# Probe.net
KiCad netlist of a schematic drawn in EAGLE
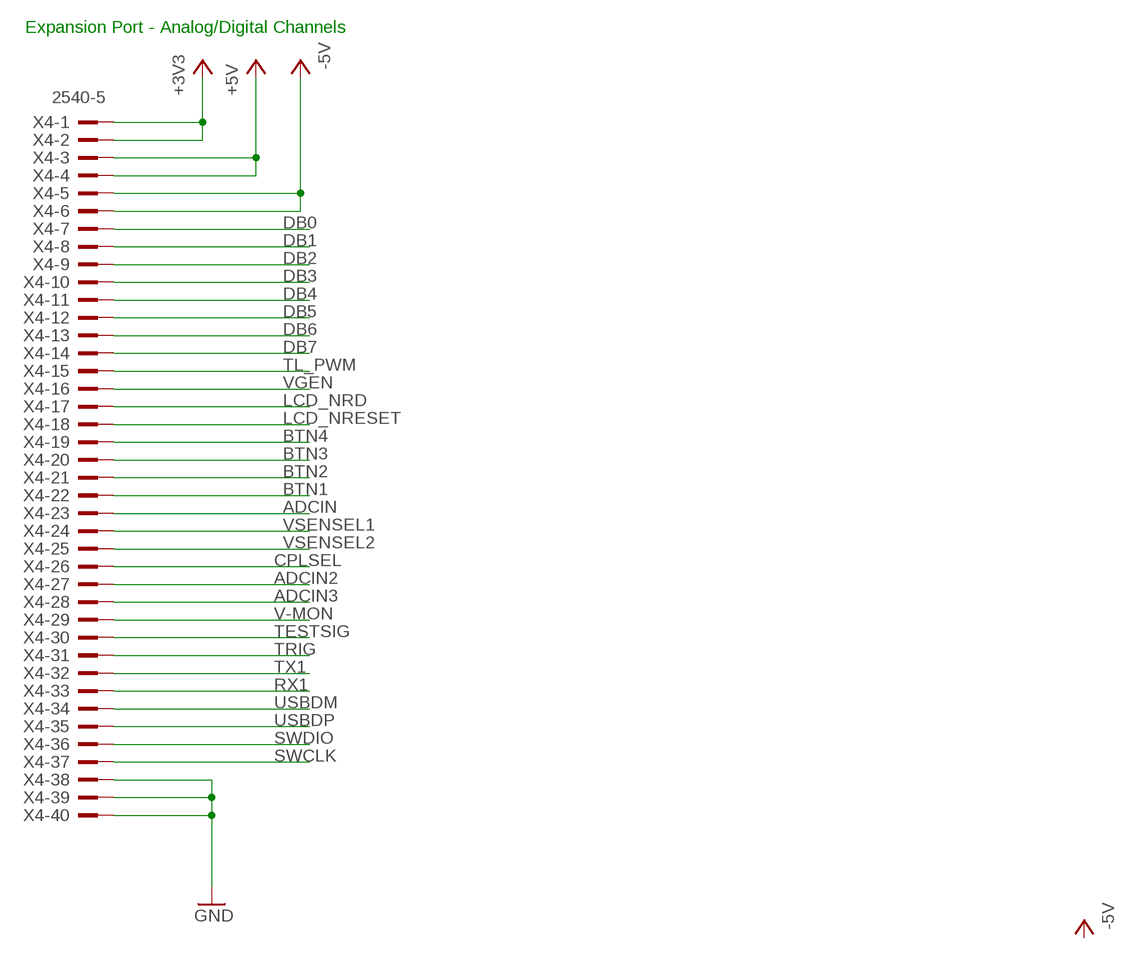
[diagram p0: schematic, sheet 1]
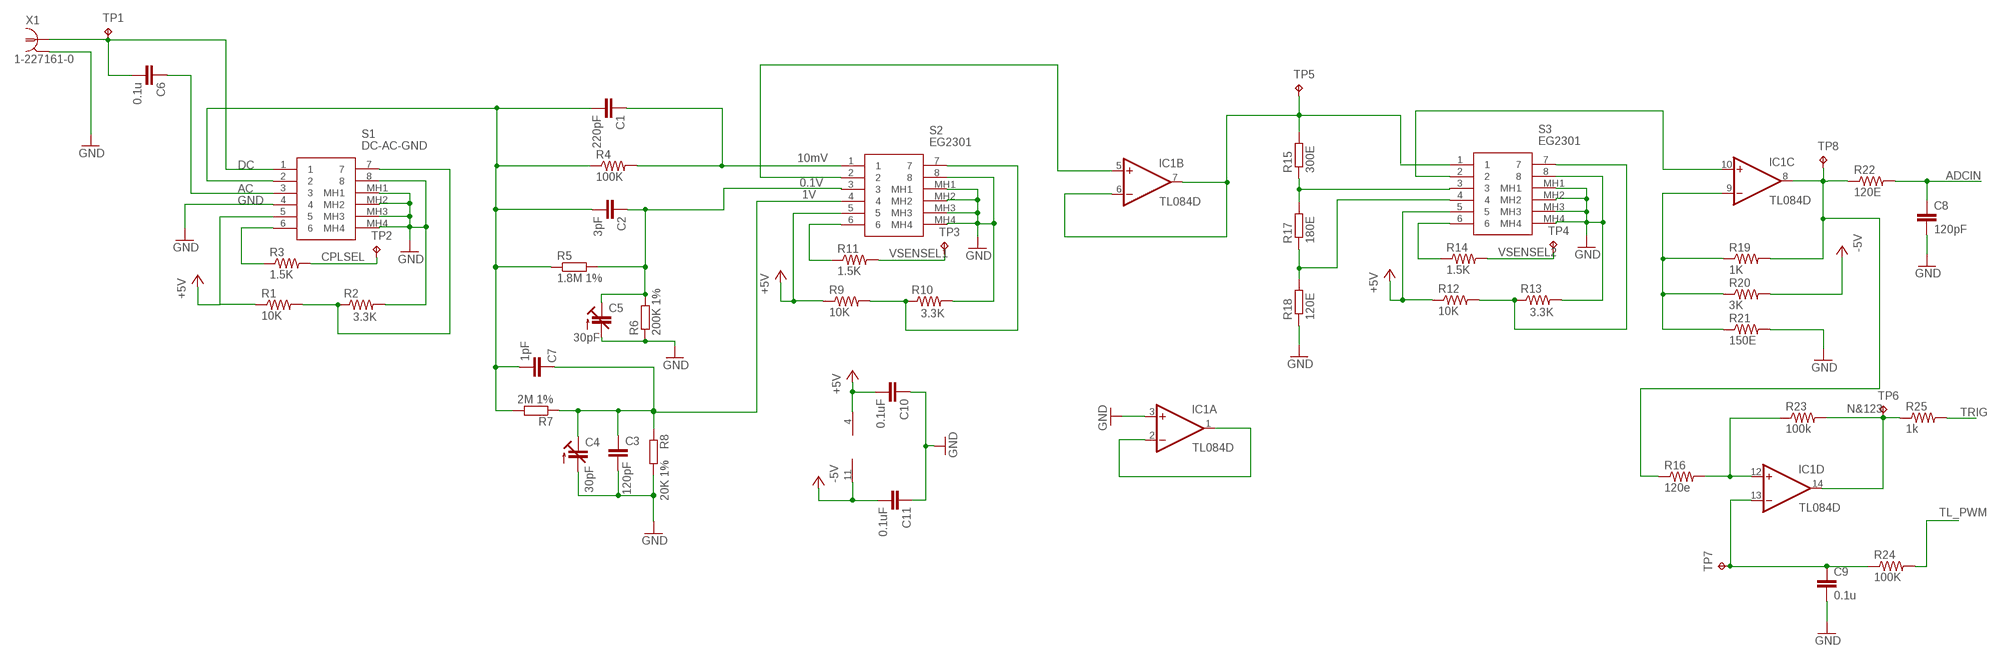
[diagram p1: schematic, sheet 2]

(export (version "E")
  (design (tool "Eeschema 10.0.6"))
  (components
    (comp (ref "C1")
      (value "220pF")
      (footprint "eagle-import:C1206")
      (libsource (lib "eagle-import") (part "C-EUC1206"))
    )
    (comp (ref "C2")
      (value "3pF")
      (footprint "eagle-import:C1206")
      (libsource (lib "eagle-import") (part "C-EUC1206"))
    )
    (comp (ref "C3")
      (value "120pF")
      (footprint "eagle-import:C2.5-3")
      (libsource (lib "eagle-import") (part "C2,5-3"))
    )
    (comp (ref "C4")
      (value "30pF")
      (footprint "eagle-import:CTRIM808-BC")
      (libsource (lib "eagle-import") (part "C-TRIMM808"))
    )
    (comp (ref "C5")
      (value "30pF")
      (footprint "eagle-import:CTRIM808-BC")
      (libsource (lib "eagle-import") (part "C-TRIMM808"))
    )
    (comp (ref "C6")
      (value "0.1u")
      (footprint "eagle-import:C1206")
      (libsource (lib "eagle-import") (part "C-EUC1206"))
    )
    (comp (ref "C7")
      (value "1pF")
      (footprint "eagle-import:C1206")
      (libsource (lib "eagle-import") (part "C-EUC1206"))
    )
    (comp (ref "C8")
      (value "120pF")
      (footprint "eagle-import:C2.5-3")
      (libsource (lib "eagle-import") (part "C2,5-3"))
    )
    (comp (ref "C9")
      (value "0.1u")
      (footprint "eagle-import:C2.5-3")
      (libsource (lib "eagle-import") (part "C2,5-3"))
    )
    (comp (ref "C10")
      (value "0.1uF")
      (footprint "eagle-import:C1206")
      (libsource (lib "eagle-import") (part "C-EUC1206"))
    )
    (comp (ref "C11")
      (value "0.1uF")
      (footprint "eagle-import:C1206")
      (libsource (lib "eagle-import") (part "C-EUC1206"))
    )
    (comp (ref "IC1")
      (value "TL084D")
      (footprint "eagle-import:SO14")
      (fields (field (name "SPICEPREFIX") "X"))
      (libsource (lib "eagle-import") (part "TL084D"))
    )
    (comp (ref "R1")
      (value "10K")
      (footprint "eagle-import:R0805")
      (libsource (lib "eagle-import") (part "R-US_R0805"))
    )
    (comp (ref "R2")
      (value "3.3K")
      (footprint "eagle-import:R0805")
      (libsource (lib "eagle-import") (part "R-US_R0805"))
    )
    (comp (ref "R3")
      (value "1.5K")
      (footprint "eagle-import:R0805")
      (libsource (lib "eagle-import") (part "R-US_R0805"))
    )
    (comp (ref "R4")
      (value "100K")
      (footprint "eagle-import:R0805")
      (libsource (lib "eagle-import") (part "R-US_R0805"))
    )
    (comp (ref "R5")
      (value "1.8M 1%")
      (footprint "eagle-import:0204_7")
      (libsource (lib "eagle-import") (part "R-EU_0204/7"))
    )
    (comp (ref "R6")
      (value "200K 1%")
      (footprint "eagle-import:0204_7")
      (libsource (lib "eagle-import") (part "R-EU_0204/7"))
    )
    (comp (ref "R7")
      (value "2M 1%")
      (footprint "eagle-import:0204_7")
      (libsource (lib "eagle-import") (part "R-EU_0204/7"))
    )
    (comp (ref "R8")
      (value "20K 1%")
      (footprint "eagle-import:0204_7")
      (libsource (lib "eagle-import") (part "R-EU_0204/7"))
    )
    (comp (ref "R9")
      (value "10K")
      (footprint "eagle-import:R0805")
      (libsource (lib "eagle-import") (part "R-US_R0805"))
    )
    (comp (ref "R10")
      (value "3.3K")
      (footprint "eagle-import:R0805")
      (libsource (lib "eagle-import") (part "R-US_R0805"))
    )
    (comp (ref "R11")
      (value "1.5K")
      (footprint "eagle-import:R0805")
      (libsource (lib "eagle-import") (part "R-US_R0805"))
    )
    (comp (ref "R12")
      (value "10K")
      (footprint "eagle-import:R0805")
      (libsource (lib "eagle-import") (part "R-US_R0805"))
    )
    (comp (ref "R13")
      (value "3.3K")
      (footprint "eagle-import:R0805")
      (libsource (lib "eagle-import") (part "R-US_R0805"))
    )
    (comp (ref "R14")
      (value "1.5K")
      (footprint "eagle-import:R0805")
      (libsource (lib "eagle-import") (part "R-US_R0805"))
    )
    (comp (ref "R15")
      (value "300E")
      (footprint "eagle-import:0204_7")
      (libsource (lib "eagle-import") (part "R-EU_0204/7"))
    )
    (comp (ref "R16")
      (value "120e")
      (footprint "eagle-import:R0805")
      (libsource (lib "eagle-import") (part "R-US_R0805"))
    )
    (comp (ref "R17")
      (value "180E")
      (footprint "eagle-import:0204_7")
      (libsource (lib "eagle-import") (part "R-EU_0204/7"))
    )
    (comp (ref "R18")
      (value "120E")
      (footprint "eagle-import:0204_7")
      (libsource (lib "eagle-import") (part "R-EU_0204/7"))
    )
    (comp (ref "R19")
      (value "1K")
      (footprint "eagle-import:R0805")
      (libsource (lib "eagle-import") (part "R-US_R0805"))
    )
    (comp (ref "R20")
      (value "3K")
      (footprint "eagle-import:R0805")
      (libsource (lib "eagle-import") (part "R-US_R0805"))
    )
    (comp (ref "R21")
      (value "150E")
      (footprint "eagle-import:R0805")
      (libsource (lib "eagle-import") (part "R-US_R0805"))
    )
    (comp (ref "R22")
      (value "120E")
      (footprint "eagle-import:R0805")
      (libsource (lib "eagle-import") (part "R-US_R0805"))
    )
    (comp (ref "R23")
      (value "100k")
      (footprint "eagle-import:R0805")
      (libsource (lib "eagle-import") (part "R-US_R0805"))
    )
    (comp (ref "R24")
      (value "100K")
      (footprint "eagle-import:R0805")
      (libsource (lib "eagle-import") (part "R-US_R0805"))
    )
    (comp (ref "R25")
      (value "1k")
      (footprint "eagle-import:R0805")
      (libsource (lib "eagle-import") (part "R-US_R0805"))
    )
    (comp (ref "S1")
      (value "DC-AC-GND")
      (footprint "eagle-import:EG2301")
      (fields
        (field (name "MANUFACTURER_PART_NUMBER") "EG2301")
        (field (name "MOUSER_PART_NUMBER") "612-EG2301")
      )
      (libsource (lib "eagle-import") (part "EG2301"))
    )
    (comp (ref "S2")
      (value "EG2301")
      (footprint "eagle-import:EG2301")
      (fields (field (name "MOUSER_PART_NUMBER") "612-EG2301"))
      (libsource (lib "eagle-import") (part "EG2301"))
    )
    (comp (ref "S3")
      (value "EG2301")
      (footprint "eagle-import:EG2301")
      (fields (field (name "MOUSER_PART_NUMBER") "612-EG2301"))
      (libsource (lib "eagle-import") (part "EG2301"))
    )
    (comp (ref "TP1")
      (value "TPB1,27")
      (footprint "eagle-import:B1,27")
      (libsource (lib "eagle-import") (part "TPB1,27"))
    )
    (comp (ref "TP2")
      (value "TPB1,27")
      (footprint "eagle-import:B1,27")
      (libsource (lib "eagle-import") (part "TPB1,27"))
    )
    (comp (ref "TP3")
      (value "TPB1,27")
      (footprint "eagle-import:B1,27")
      (libsource (lib "eagle-import") (part "TPB1,27"))
    )
    (comp (ref "TP4")
      (value "TPB1,27")
      (footprint "eagle-import:B1,27")
      (libsource (lib "eagle-import") (part "TPB1,27"))
    )
    (comp (ref "TP5")
      (value "TPB1,27")
      (footprint "eagle-import:B1,27")
      (libsource (lib "eagle-import") (part "TPB1,27"))
    )
    (comp (ref "TP6")
      (value "TPB1,27")
      (footprint "eagle-import:B1,27")
      (libsource (lib "eagle-import") (part "TPB1,27"))
    )
    (comp (ref "TP7")
      (value "TPB1,27")
      (footprint "eagle-import:B1,27")
      (libsource (lib "eagle-import") (part "TPB1,27"))
    )
    (comp (ref "TP8")
      (value "TPB1,27")
      (footprint "eagle-import:B1,27")
      (libsource (lib "eagle-import") (part "TPB1,27"))
    )
    (comp (ref "X1")
      (value "1-227161-0")
      (footprint "eagle-import:AMP_227161")
      (fields (field (name "MF") "TYCO ELECTRONICS") (field (name "MPN") "1-227161"))
      (libsource (lib "eagle-import") (part "?2271611--0"))
    )
    (comp (ref "X4")
      (value "2540-5")
      (footprint "eagle-import:PAK100_2500-5-40")
      (libsource (lib "eagle-import") (part "2540-5"))
    )
  )
  (nets
    (net (code "1") (name "+3V3") (class "Default")
      (node (ref "X4") (pin "1") (pinfunction "KL_1") (pintype "passive"))
      (node (ref "X4") (pin "2") (pinfunction "KL_2") (pintype "passive"))
    )
    (net (code "2") (name "+5V") (class "Default")
      (node (ref "C10") (pin "2") (pinfunction "2_2") (pintype "passive"))
      (node (ref "IC1") (pin "4") (pinfunction "V+_4") (pintype "power_in"))
      (node (ref "R1") (pin "1") (pinfunction "1_1") (pintype "passive"))
      (node (ref "R12") (pin "1") (pinfunction "1_1") (pintype "passive"))
      (node (ref "R9") (pin "1") (pinfunction "1_1") (pintype "passive"))
      (node (ref "S1") (pin "5") (pinfunction "5_5") (pintype "bidirectional"))
      (node (ref "S2") (pin "5") (pinfunction "5_5") (pintype "bidirectional"))
      (node (ref "S3") (pin "5") (pinfunction "5_5") (pintype "bidirectional"))
      (node (ref "X4") (pin "3") (pinfunction "KL_3") (pintype "passive"))
      (node (ref "X4") (pin "4") (pinfunction "KL_4") (pintype "passive"))
    )
    (net (code "3") (name "-5V") (class "Default")
      (node (ref "C11") (pin "2") (pinfunction "2_2") (pintype "passive"))
      (node (ref "IC1") (pin "11") (pinfunction "V-_11") (pintype "power_in"))
      (node (ref "R20") (pin "2") (pinfunction "2_2") (pintype "passive"))
      (node (ref "X4") (pin "5") (pinfunction "KL_5") (pintype "passive"))
      (node (ref "X4") (pin "6") (pinfunction "KL_6") (pintype "passive"))
    )
    (net (code "4") (name "ADCIN") (class "Default")
      (node (ref "C8") (pin "1") (pinfunction "1_1") (pintype "passive"))
      (node (ref "R22") (pin "2") (pinfunction "2_2") (pintype "passive"))
      (node (ref "X4") (pin "23") (pinfunction "KL_23") (pintype "passive"))
    )
    (net (code "5") (name "ADCIN2") (class "Default")
      (node (ref "X4") (pin "27") (pinfunction "KL_27") (pintype "passive"))
    )
    (net (code "6") (name "ADCIN3") (class "Default")
      (node (ref "X4") (pin "28") (pinfunction "KL_28") (pintype "passive"))
    )
    (net (code "7") (name "BTN1") (class "Default")
      (node (ref "X4") (pin "22") (pinfunction "KL_22") (pintype "passive"))
    )
    (net (code "8") (name "BTN2") (class "Default")
      (node (ref "X4") (pin "21") (pinfunction "KL_21") (pintype "passive"))
    )
    (net (code "9") (name "BTN3") (class "Default")
      (node (ref "X4") (pin "20") (pinfunction "KL_20") (pintype "passive"))
    )
    (net (code "10") (name "BTN4") (class "Default")
      (node (ref "X4") (pin "19") (pinfunction "KL_19") (pintype "passive"))
    )
    (net (code "11") (name "CPLSEL") (class "Default")
      (node (ref "R3") (pin "2") (pinfunction "2_2") (pintype "passive"))
      (node (ref "TP2") (pin "TP") (pinfunction "TP_TP") (pintype "input"))
      (node (ref "X4") (pin "26") (pinfunction "KL_26") (pintype "passive"))
    )
    (net (code "12") (name "DB0") (class "Default")
      (node (ref "X4") (pin "7") (pinfunction "KL_7") (pintype "passive"))
    )
    (net (code "13") (name "DB1") (class "Default")
      (node (ref "X4") (pin "8") (pinfunction "KL_8") (pintype "passive"))
    )
    (net (code "14") (name "DB2") (class "Default")
      (node (ref "X4") (pin "9") (pinfunction "KL_9") (pintype "passive"))
    )
    (net (code "15") (name "DB3") (class "Default")
      (node (ref "X4") (pin "10") (pinfunction "KL_10") (pintype "passive"))
    )
    (net (code "16") (name "DB4") (class "Default")
      (node (ref "X4") (pin "11") (pinfunction "KL_11") (pintype "passive"))
    )
    (net (code "17") (name "DB5") (class "Default")
      (node (ref "X4") (pin "12") (pinfunction "KL_12") (pintype "passive"))
    )
    (net (code "18") (name "DB6") (class "Default")
      (node (ref "X4") (pin "13") (pinfunction "KL_13") (pintype "passive"))
    )
    (net (code "19") (name "DB7") (class "Default")
      (node (ref "X4") (pin "14") (pinfunction "KL_14") (pintype "passive"))
    )
    (net (code "20") (name "GND") (class "Default")
      (node (ref "C10") (pin "1") (pinfunction "1_1") (pintype "passive"))
      (node (ref "C11") (pin "1") (pinfunction "1_1") (pintype "passive"))
      (node (ref "C3") (pin "2") (pinfunction "2_2") (pintype "passive"))
      (node (ref "C4") (pin "2") (pinfunction "A_2") (pintype "passive"))
      (node (ref "C5") (pin "2") (pinfunction "A_2") (pintype "passive"))
      (node (ref "C8") (pin "2") (pinfunction "2_2") (pintype "passive"))
      (node (ref "C9") (pin "2") (pinfunction "2_2") (pintype "passive"))
      (node (ref "IC1") (pin "3") (pinfunction "+IN_3") (pintype "input"))
      (node (ref "R10") (pin "2") (pinfunction "2_2") (pintype "passive"))
      (node (ref "R13") (pin "2") (pinfunction "2_2") (pintype "passive"))
      (node (ref "R18") (pin "1") (pinfunction "1_1") (pintype "passive"))
      (node (ref "R2") (pin "2") (pinfunction "2_2") (pintype "passive"))
      (node (ref "R21") (pin "2") (pinfunction "2_2") (pintype "passive"))
      (node (ref "R6") (pin "1") (pinfunction "1_1") (pintype "passive"))
      (node (ref "R8") (pin "2") (pinfunction "2_2") (pintype "passive"))
      (node (ref "S1") (pin "4") (pinfunction "4_4") (pintype "bidirectional"))
      (node (ref "S1") (pin "8") (pinfunction "8_8") (pintype "bidirectional"))
      (node (ref "S1") (pin "MH1") (pinfunction "MH1_MH1") (pintype "bidirectional"))
      (node (ref "S1") (pin "MH2") (pinfunction "MH2_MH2") (pintype "bidirectional"))
      (node (ref "S1") (pin "MH3") (pinfunction "MH3_MH3") (pintype "bidirectional"))
      (node (ref "S1") (pin "MH4") (pinfunction "MH4_MH4") (pintype "bidirectional"))
      (node (ref "S2") (pin "8") (pinfunction "8_8") (pintype "bidirectional"))
      (node (ref "S2") (pin "MH1") (pinfunction "MH1_MH1") (pintype "bidirectional"))
      (node (ref "S2") (pin "MH2") (pinfunction "MH2_MH2") (pintype "bidirectional"))
      (node (ref "S2") (pin "MH3") (pinfunction "MH3_MH3") (pintype "bidirectional"))
      (node (ref "S2") (pin "MH4") (pinfunction "MH4_MH4") (pintype "bidirectional"))
      (node (ref "S3") (pin "8") (pinfunction "8_8") (pintype "bidirectional"))
      (node (ref "S3") (pin "MH1") (pinfunction "MH1_MH1") (pintype "bidirectional"))
      (node (ref "S3") (pin "MH2") (pinfunction "MH2_MH2") (pintype "bidirectional"))
      (node (ref "S3") (pin "MH3") (pinfunction "MH3_MH3") (pintype "bidirectional"))
      (node (ref "S3") (pin "MH4") (pinfunction "MH4_MH4") (pintype "bidirectional"))
      (node (ref "X1") (pin "2") (pinfunction "2_2") (pintype "passive"))
      (node (ref "X4") (pin "38") (pinfunction "KL_38") (pintype "passive"))
      (node (ref "X4") (pin "39") (pinfunction "KL_39") (pintype "passive"))
      (node (ref "X4") (pin "40") (pinfunction "KL_40") (pintype "passive"))
    )
    (net (code "21") (name "LCD_NRD") (class "Default")
      (node (ref "X4") (pin "17") (pinfunction "KL_17") (pintype "passive"))
    )
    (net (code "22") (name "LCD_NRESET") (class "Default")
      (node (ref "X4") (pin "18") (pinfunction "KL_18") (pintype "passive"))
    )
    (net (code "23") (name "N&123") (class "Default")
      (node (ref "IC1") (pin "14") (pinfunction "OUT_14") (pintype "output"))
      (node (ref "R23") (pin "2") (pinfunction "2_2") (pintype "passive"))
      (node (ref "R25") (pin "1") (pinfunction "1_1") (pintype "passive"))
      (node (ref "TP6") (pin "TP") (pinfunction "TP_TP") (pintype "input"))
    )
    (net (code "24") (name "Net-(C1-Pad1)") (class "Default")
      (node (ref "C1") (pin "1") (pinfunction "1_1") (pintype "passive"))
      (node (ref "R4") (pin "2") (pinfunction "2_2") (pintype "passive"))
      (node (ref "S2") (pin "1") (pinfunction "1_1") (pintype "bidirectional"))
    )
    (net (code "25") (name "Net-(C1-Pad2)") (class "Default")
      (node (ref "C1") (pin "2") (pinfunction "2_2") (pintype "passive"))
      (node (ref "C2") (pin "2") (pinfunction "2_2") (pintype "passive"))
      (node (ref "C7") (pin "2") (pinfunction "2_2") (pintype "passive"))
      (node (ref "R4") (pin "1") (pinfunction "1_1") (pintype "passive"))
      (node (ref "R5") (pin "1") (pinfunction "1_1") (pintype "passive"))
      (node (ref "R7") (pin "2") (pinfunction "2_2") (pintype "passive"))
      (node (ref "S1") (pin "2") (pinfunction "2_2") (pintype "bidirectional"))
    )
    (net (code "26") (name "Net-(C4-E)") (class "Default")
      (node (ref "C3") (pin "1") (pinfunction "1_1") (pintype "passive"))
      (node (ref "C4") (pin "1") (pinfunction "E_1") (pintype "passive"))
      (node (ref "C7") (pin "1") (pinfunction "1_1") (pintype "passive"))
      (node (ref "R7") (pin "1") (pinfunction "1_1") (pintype "passive"))
      (node (ref "R8") (pin "1") (pinfunction "1_1") (pintype "passive"))
      (node (ref "S2") (pin "4") (pinfunction "4_4") (pintype "bidirectional"))
    )
    (net (code "27") (name "Net-(C5-E)") (class "Default")
      (node (ref "C2") (pin "1") (pinfunction "1_1") (pintype "passive"))
      (node (ref "C5") (pin "1") (pinfunction "E_1") (pintype "passive"))
      (node (ref "R5") (pin "2") (pinfunction "2_2") (pintype "passive"))
      (node (ref "R6") (pin "2") (pinfunction "2_2") (pintype "passive"))
      (node (ref "S2") (pin "3") (pinfunction "3_3") (pintype "bidirectional"))
    )
    (net (code "28") (name "Net-(C6-Pad1)") (class "Default")
      (node (ref "C6") (pin "1") (pinfunction "1_1") (pintype "passive"))
      (node (ref "S1") (pin "3") (pinfunction "3_3") (pintype "bidirectional"))
    )
    (net (code "29") (name "Net-(C6-Pad2)") (class "Default")
      (node (ref "C6") (pin "2") (pinfunction "2_2") (pintype "passive"))
      (node (ref "S1") (pin "1") (pinfunction "1_1") (pintype "bidirectional"))
      (node (ref "TP1") (pin "TP") (pinfunction "TP_TP") (pintype "input"))
      (node (ref "X1") (pin "1") (pinfunction "1_1") (pintype "passive"))
    )
    (net (code "30") (name "Net-(IC1A--IN)") (class "Default")
      (node (ref "IC1") (pin "1") (pinfunction "OUT_1") (pintype "output"))
      (node (ref "IC1") (pin "2") (pinfunction "-IN_2") (pintype "input"))
    )
    (net (code "31") (name "Net-(IC1B-+IN)") (class "Default")
      (node (ref "IC1") (pin "5") (pinfunction "+IN_5") (pintype "input"))
      (node (ref "S2") (pin "2") (pinfunction "2_2") (pintype "bidirectional"))
    )
    (net (code "32") (name "Net-(IC1B--IN)") (class "Default")
      (node (ref "IC1") (pin "6") (pinfunction "-IN_6") (pintype "input"))
      (node (ref "IC1") (pin "7") (pinfunction "OUT_7") (pintype "output"))
      (node (ref "R15") (pin "2") (pinfunction "2_2") (pintype "passive"))
      (node (ref "TP5") (pin "TP") (pinfunction "TP_TP") (pintype "input"))
    )
    (net (code "33") (name "Net-(IC1C-+IN)") (class "Default")
      (node (ref "IC1") (pin "10") (pinfunction "+IN_10") (pintype "input"))
      (node (ref "S3") (pin "2") (pinfunction "2_2") (pintype "bidirectional"))
    )
    (net (code "34") (name "Net-(IC1C--IN)") (class "Default")
      (node (ref "IC1") (pin "9") (pinfunction "-IN_9") (pintype "input"))
      (node (ref "R19") (pin "1") (pinfunction "1_1") (pintype "passive"))
      (node (ref "R20") (pin "1") (pinfunction "1_1") (pintype "passive"))
      (node (ref "R21") (pin "1") (pinfunction "1_1") (pintype "passive"))
    )
    (net (code "35") (name "Net-(IC1C-OUT)") (class "Default")
      (node (ref "IC1") (pin "8") (pinfunction "OUT_8") (pintype "output"))
      (node (ref "R16") (pin "1") (pinfunction "1_1") (pintype "passive"))
      (node (ref "R19") (pin "2") (pinfunction "2_2") (pintype "passive"))
      (node (ref "R22") (pin "1") (pinfunction "1_1") (pintype "passive"))
      (node (ref "TP8") (pin "TP") (pinfunction "TP_TP") (pintype "input"))
    )
    (net (code "36") (name "Net-(IC1D-+IN)") (class "Default")
      (node (ref "IC1") (pin "12") (pinfunction "+IN_12") (pintype "input"))
      (node (ref "R16") (pin "2") (pinfunction "2_2") (pintype "passive"))
      (node (ref "R23") (pin "1") (pinfunction "1_1") (pintype "passive"))
    )
    (net (code "37") (name "Net-(IC1D--IN)") (class "Default")
      (node (ref "C9") (pin "1") (pinfunction "1_1") (pintype "passive"))
      (node (ref "IC1") (pin "13") (pinfunction "-IN_13") (pintype "input"))
      (node (ref "R24") (pin "1") (pinfunction "1_1") (pintype "passive"))
      (node (ref "TP7") (pin "TP") (pinfunction "TP_TP") (pintype "input"))
    )
    (net (code "38") (name "Net-(R1-Pad2)") (class "Default")
      (node (ref "R1") (pin "2") (pinfunction "2_2") (pintype "passive"))
      (node (ref "R2") (pin "1") (pinfunction "1_1") (pintype "passive"))
      (node (ref "S1") (pin "7") (pinfunction "7_7") (pintype "bidirectional"))
    )
    (net (code "39") (name "Net-(R3-Pad1)") (class "Default")
      (node (ref "R3") (pin "1") (pinfunction "1_1") (pintype "passive"))
      (node (ref "S1") (pin "6") (pinfunction "6_6") (pintype "bidirectional"))
    )
    (net (code "40") (name "Net-(R10-Pad1)") (class "Default")
      (node (ref "R10") (pin "1") (pinfunction "1_1") (pintype "passive"))
      (node (ref "R9") (pin "2") (pinfunction "2_2") (pintype "passive"))
      (node (ref "S2") (pin "7") (pinfunction "7_7") (pintype "bidirectional"))
    )
    (net (code "41") (name "Net-(R11-Pad1)") (class "Default")
      (node (ref "R11") (pin "1") (pinfunction "1_1") (pintype "passive"))
      (node (ref "S2") (pin "6") (pinfunction "6_6") (pintype "bidirectional"))
    )
    (net (code "42") (name "Net-(R12-Pad2)") (class "Default")
      (node (ref "R12") (pin "2") (pinfunction "2_2") (pintype "passive"))
      (node (ref "R13") (pin "1") (pinfunction "1_1") (pintype "passive"))
      (node (ref "S3") (pin "7") (pinfunction "7_7") (pintype "bidirectional"))
    )
    (net (code "43") (name "Net-(R14-Pad1)") (class "Default")
      (node (ref "R14") (pin "1") (pinfunction "1_1") (pintype "passive"))
      (node (ref "S3") (pin "6") (pinfunction "6_6") (pintype "bidirectional"))
    )
    (net (code "44") (name "Net-(R15-Pad1)") (class "Default")
      (node (ref "R15") (pin "1") (pinfunction "1_1") (pintype "passive"))
      (node (ref "R17") (pin "2") (pinfunction "2_2") (pintype "passive"))
      (node (ref "S3") (pin "3") (pinfunction "3_3") (pintype "bidirectional"))
    )
    (net (code "45") (name "Net-(R17-Pad1)") (class "Default")
      (node (ref "R17") (pin "1") (pinfunction "1_1") (pintype "passive"))
      (node (ref "R18") (pin "2") (pinfunction "2_2") (pintype "passive"))
      (node (ref "S3") (pin "4") (pinfunction "4_4") (pintype "bidirectional"))
    )
    (net (code "46") (name "RX1") (class "Default")
      (node (ref "X4") (pin "33") (pinfunction "KL_33") (pintype "passive"))
    )
    (net (code "47") (name "SWCLK") (class "Default")
      (node (ref "X4") (pin "37") (pinfunction "KL_37") (pintype "passive"))
    )
    (net (code "48") (name "SWDIO") (class "Default")
      (node (ref "X4") (pin "36") (pinfunction "KL_36") (pintype "passive"))
    )
    (net (code "49") (name "TESTSIG") (class "Default")
      (node (ref "X4") (pin "30") (pinfunction "KL_30") (pintype "passive"))
    )
    (net (code "50") (name "TL_PWM") (class "Default")
      (node (ref "R24") (pin "2") (pinfunction "2_2") (pintype "passive"))
      (node (ref "X4") (pin "15") (pinfunction "KL_15") (pintype "passive"))
    )
    (net (code "51") (name "TRIG") (class "Default")
      (node (ref "R25") (pin "2") (pinfunction "2_2") (pintype "passive"))
      (node (ref "X4") (pin "31") (pinfunction "KL_31") (pintype "passive"))
    )
    (net (code "52") (name "TX1") (class "Default")
      (node (ref "X4") (pin "32") (pinfunction "KL_32") (pintype "passive"))
    )
    (net (code "53") (name "USBDM") (class "Default")
      (node (ref "X4") (pin "34") (pinfunction "KL_34") (pintype "passive"))
    )
    (net (code "54") (name "USBDP") (class "Default")
      (node (ref "X4") (pin "35") (pinfunction "KL_35") (pintype "passive"))
    )
    (net (code "55") (name "V-MON") (class "Default")
      (node (ref "X4") (pin "29") (pinfunction "KL_29") (pintype "passive"))
    )
    (net (code "56") (name "VGEN") (class "Default")
      (node (ref "X4") (pin "16") (pinfunction "KL_16") (pintype "passive"))
    )
    (net (code "57") (name "VSENSEL1") (class "Default")
      (node (ref "R11") (pin "2") (pinfunction "2_2") (pintype "passive"))
      (node (ref "TP3") (pin "TP") (pinfunction "TP_TP") (pintype "input"))
      (node (ref "X4") (pin "24") (pinfunction "KL_24") (pintype "passive"))
    )
    (net (code "58") (name "VSENSEL2") (class "Default")
      (node (ref "R14") (pin "2") (pinfunction "2_2") (pintype "passive"))
      (node (ref "TP4") (pin "TP") (pinfunction "TP_TP") (pintype "input"))
      (node (ref "X4") (pin "25") (pinfunction "KL_25") (pintype "passive"))
    )
    (net (code "59") (name "unconnected-(S3-Pad1)") (class "Default")
      (node (ref "S3") (pin "1") (pinfunction "1_1") (pintype "bidirectional"))
    )
  )
)
